# Connectors.net
KiCad netlist of a schematic drawn in Altium Designer
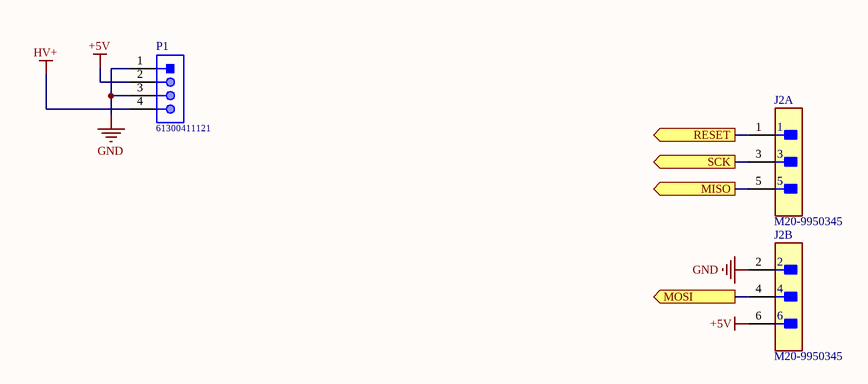
[diagram p0: Connectors.SchDoc]

(export (version "E")
  (design (tool "Eeschema 10.0.6"))
  (components
    (comp (ref "J2")
      (value "M20-9950345")
      (footprint "FP-M20-9950345-MFG")
      (description "CONN HEADER R/A 6POS 2.54MM")
      (fields
        (field (name "OCTOPART") "https://octopart.com/m20-9950345-harwin-21265213")
        (field (name "MANUFACTURER") "Harwin")
      )
      (libsource (lib "Altium Content Vault") (part "b76336891f9c52daa0497ceff74f613"))
    )
    (comp (ref "P1")
      (value "61300411121")
      (footprint "61300411121")
      (description "THT Vertical Pin Header WR-PHD, Pitch 2.54 mm, Single Row, 4 pins")
      (fields (field (name "MANUFACTURER") "Wurth Elektronik") (field (name "PUBLISHER") "WurthElektronik"))
      (libsource (lib "Altium Content Vault") (part "WE-CN-1P-M-R4"))
    )
  )
  (nets
    (net (code "1") (name "+5V") (class "Default")
      (node (ref "J2") (pin "6") (pinfunction "6_6") (pintype "passive"))
      (node (ref "P1") (pin "2") (pinfunction "2_2") (pintype "passive"))
    )
    (net (code "2") (name "/MISO") (class "Default")
      (node (ref "J2") (pin "5") (pinfunction "5_5") (pintype "passive"))
    )
    (net (code "3") (name "/MOSI") (class "Default")
      (node (ref "J2") (pin "4") (pinfunction "4_4") (pintype "passive"))
    )
    (net (code "4") (name "/RESET") (class "Default")
      (node (ref "J2") (pin "1") (pinfunction "1_1") (pintype "passive"))
    )
    (net (code "5") (name "/SCK") (class "Default")
      (node (ref "J2") (pin "3") (pinfunction "3_3") (pintype "passive"))
    )
    (net (code "6") (name "GND") (class "Default")
      (node (ref "J2") (pin "2") (pinfunction "2_2") (pintype "passive"))
      (node (ref "P1") (pin "1") (pinfunction "1_1") (pintype "passive"))
      (node (ref "P1") (pin "3") (pinfunction "3_3") (pintype "passive"))
    )
    (net (code "7") (name "HV+") (class "Default")
      (node (ref "P1") (pin "4") (pinfunction "4_4") (pintype "passive"))
    )
  )
)
